# module_CKP_Hall.net
KiCad netlist of a schematic drawn in EAGLE
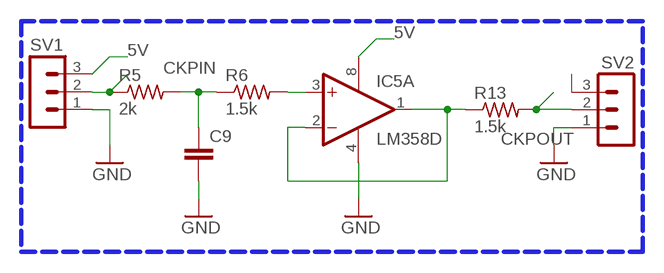
[diagram p0: schematic, sheet 1]

(export (version "E")
  (design (tool "Eeschema 10.0.6"))
  (components
    (comp (ref "C9")
      (value "C-EU025-025X050")
      (footprint "eagle-import:C025-025X050")
      (libsource (lib "eagle-import") (part "C-EU025-025X050"))
    )
    (comp (ref "IC5")
      (value "LM358D")
      (footprint "eagle-import:SO08")
      (libsource (lib "eagle-import") (part "LM358D"))
    )
    (comp (ref "R5")
      (value "2k")
      (footprint "eagle-import:0204_5")
      (libsource (lib "eagle-import") (part "R-US_0204/5"))
    )
    (comp (ref "R6")
      (value "1.5k")
      (footprint "eagle-import:0204_5")
      (libsource (lib "eagle-import") (part "R-US_0204/5"))
    )
    (comp (ref "R13")
      (value "1.5k")
      (footprint "eagle-import:0204_5")
      (libsource (lib "eagle-import") (part "R-US_0204/5"))
    )
    (comp (ref "SV1")
      (value "MA03-1")
      (footprint "eagle-import:MA03-1")
      (libsource (lib "eagle-import") (part "MA03-1"))
    )
    (comp (ref "SV2")
      (value "MA03-1")
      (footprint "eagle-import:MA03-1")
      (libsource (lib "eagle-import") (part "MA03-1"))
    )
  )
  (nets
    (net (code "1") (name "/5V") (class "Default")
      (node (ref "IC5") (pin "8") (pinfunction "V+_8") (pintype "power_in"))
      (node (ref "SV1") (pin "3") (pinfunction "3_3") (pintype "passive"))
    )
    (net (code "2") (name "/CKPIN") (class "Default")
      (node (ref "R5") (pin "1") (pinfunction "1_1") (pintype "passive"))
      (node (ref "SV1") (pin "2") (pinfunction "2_2") (pintype "passive"))
    )
    (net (code "3") (name "/CKPOUT") (class "Default")
      (node (ref "R13") (pin "2") (pinfunction "2_2") (pintype "passive"))
      (node (ref "SV2") (pin "2") (pinfunction "2_2") (pintype "passive"))
    )
    (net (code "4") (name "GND") (class "Default")
      (node (ref "C9") (pin "2") (pinfunction "2_2") (pintype "passive"))
      (node (ref "IC5") (pin "4") (pinfunction "V-_4") (pintype "power_in"))
      (node (ref "SV1") (pin "1") (pinfunction "1_1") (pintype "passive"))
      (node (ref "SV2") (pin "1") (pinfunction "1_1") (pintype "passive"))
    )
    (net (code "5") (name "Net-(C9-Pad1)") (class "Default")
      (node (ref "C9") (pin "1") (pinfunction "1_1") (pintype "passive"))
      (node (ref "R5") (pin "2") (pinfunction "2_2") (pintype "passive"))
      (node (ref "R6") (pin "1") (pinfunction "1_1") (pintype "passive"))
    )
    (net (code "6") (name "Net-(IC5A-+IN)") (class "Default")
      (node (ref "IC5") (pin "3") (pinfunction "+IN_3") (pintype "input"))
      (node (ref "R6") (pin "2") (pinfunction "2_2") (pintype "passive"))
    )
    (net (code "7") (name "Net-(IC5A--IN)") (class "Default")
      (node (ref "IC5") (pin "1") (pinfunction "OUT_1") (pintype "output"))
      (node (ref "IC5") (pin "2") (pinfunction "-IN_2") (pintype "input"))
      (node (ref "R13") (pin "1") (pinfunction "1_1") (pintype "passive"))
    )
    (net (code "8") (name "unconnected-(SV2-Pad3)") (class "Default")
      (node (ref "SV2") (pin "3") (pinfunction "3_3") (pintype "passive"))
    )
  )
)
